# cpu-68008.net
KiCad netlist of a schematic drawn in EAGLE
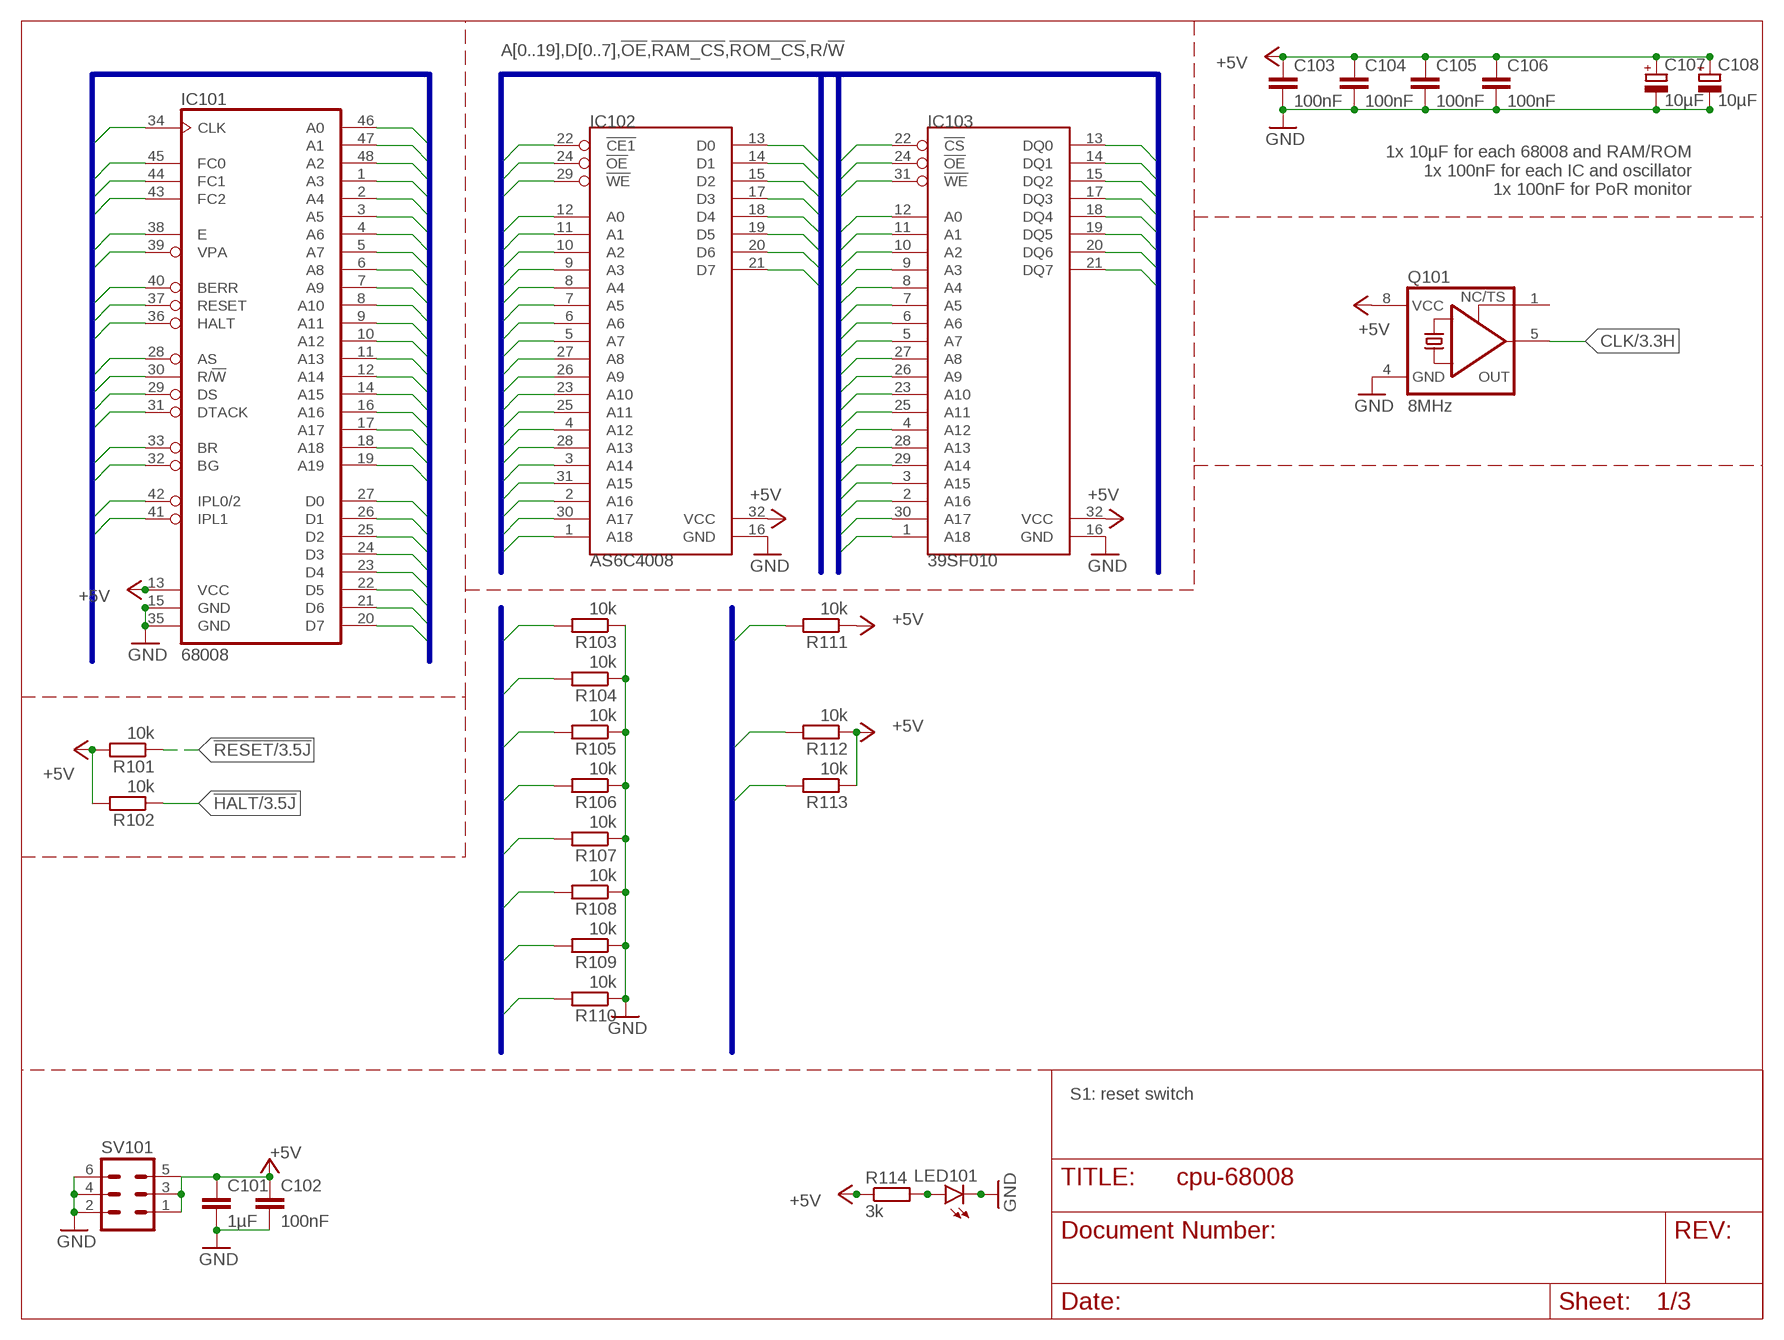
[diagram p0: schematic, sheet 1]
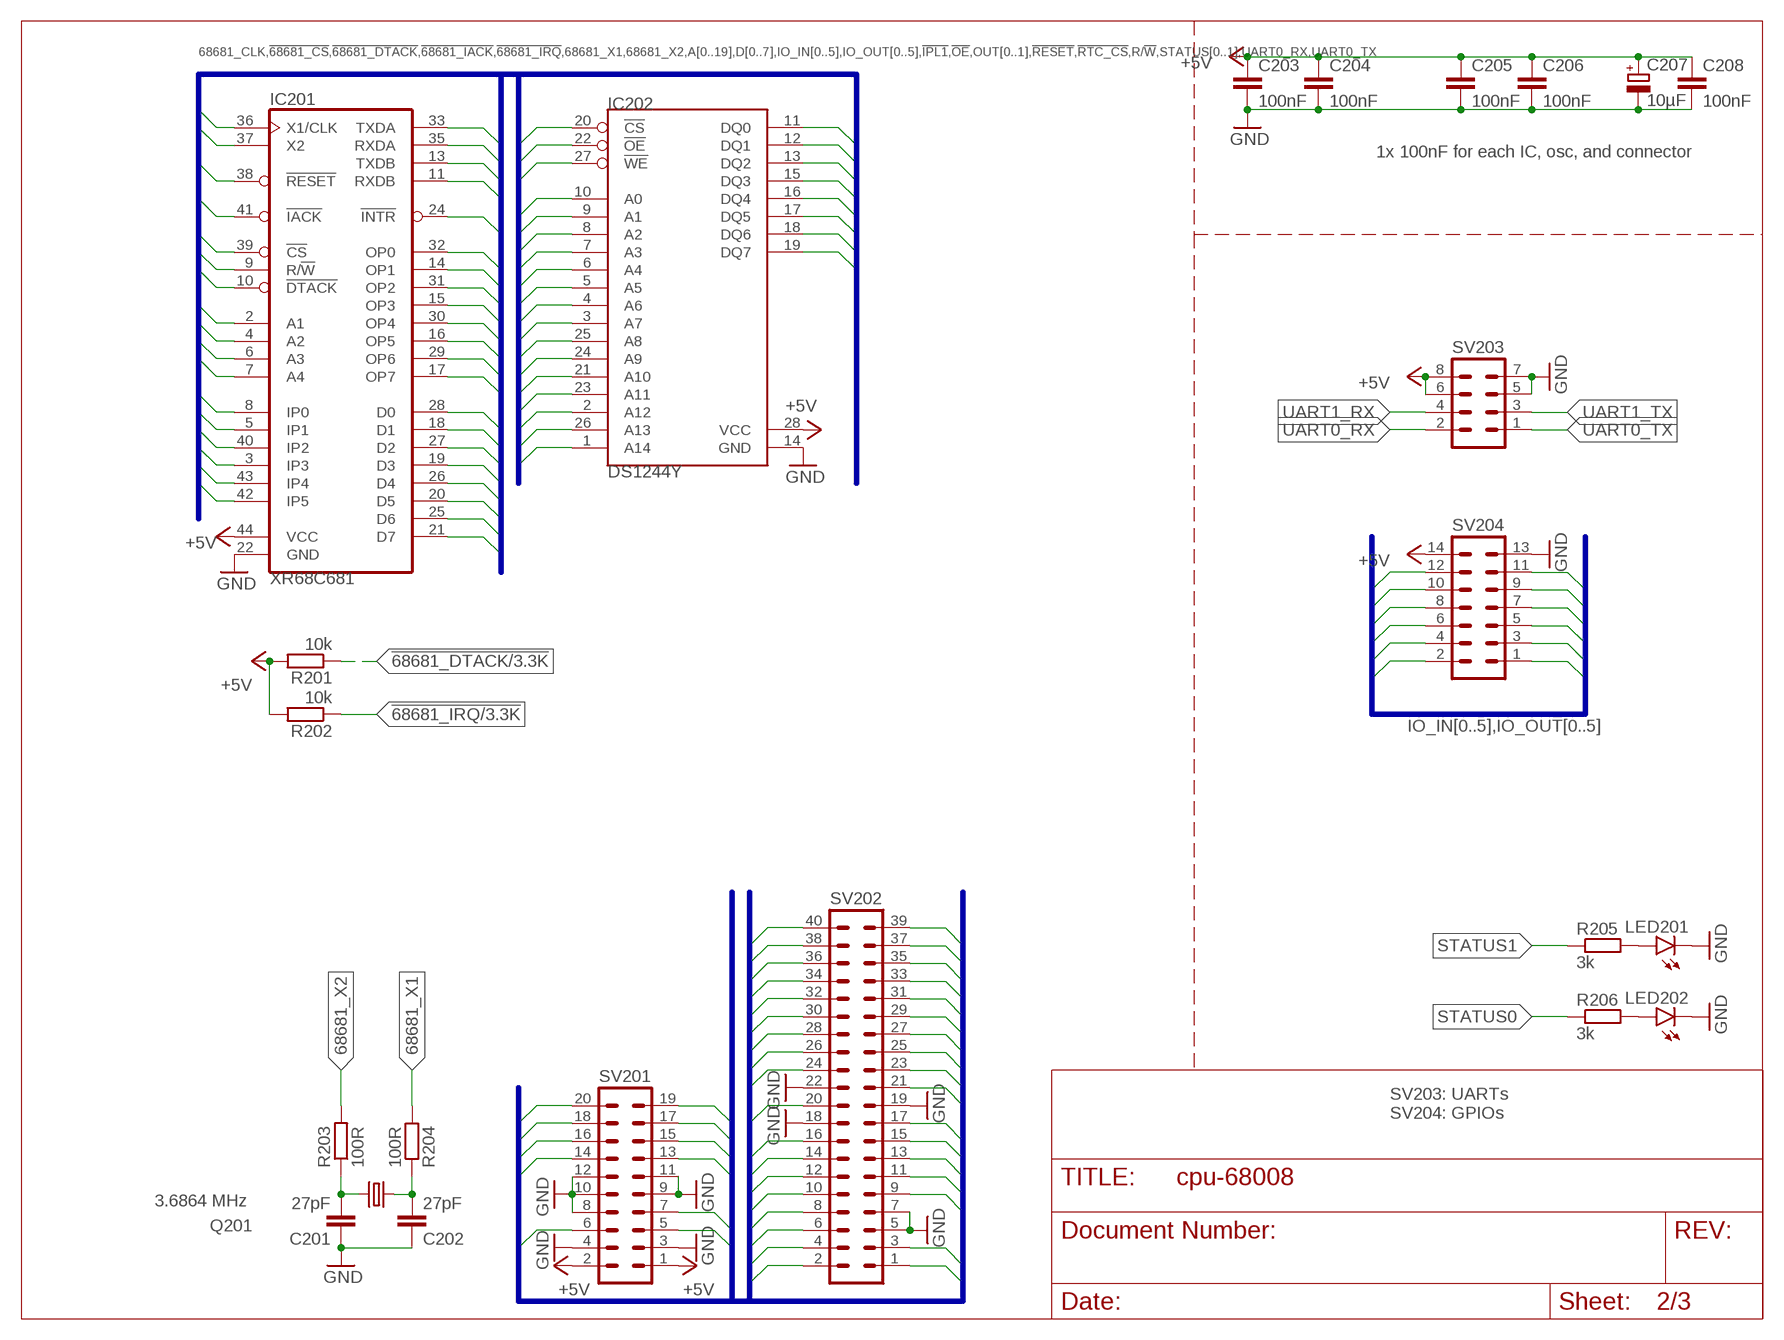
[diagram p1: schematic, sheet 2]
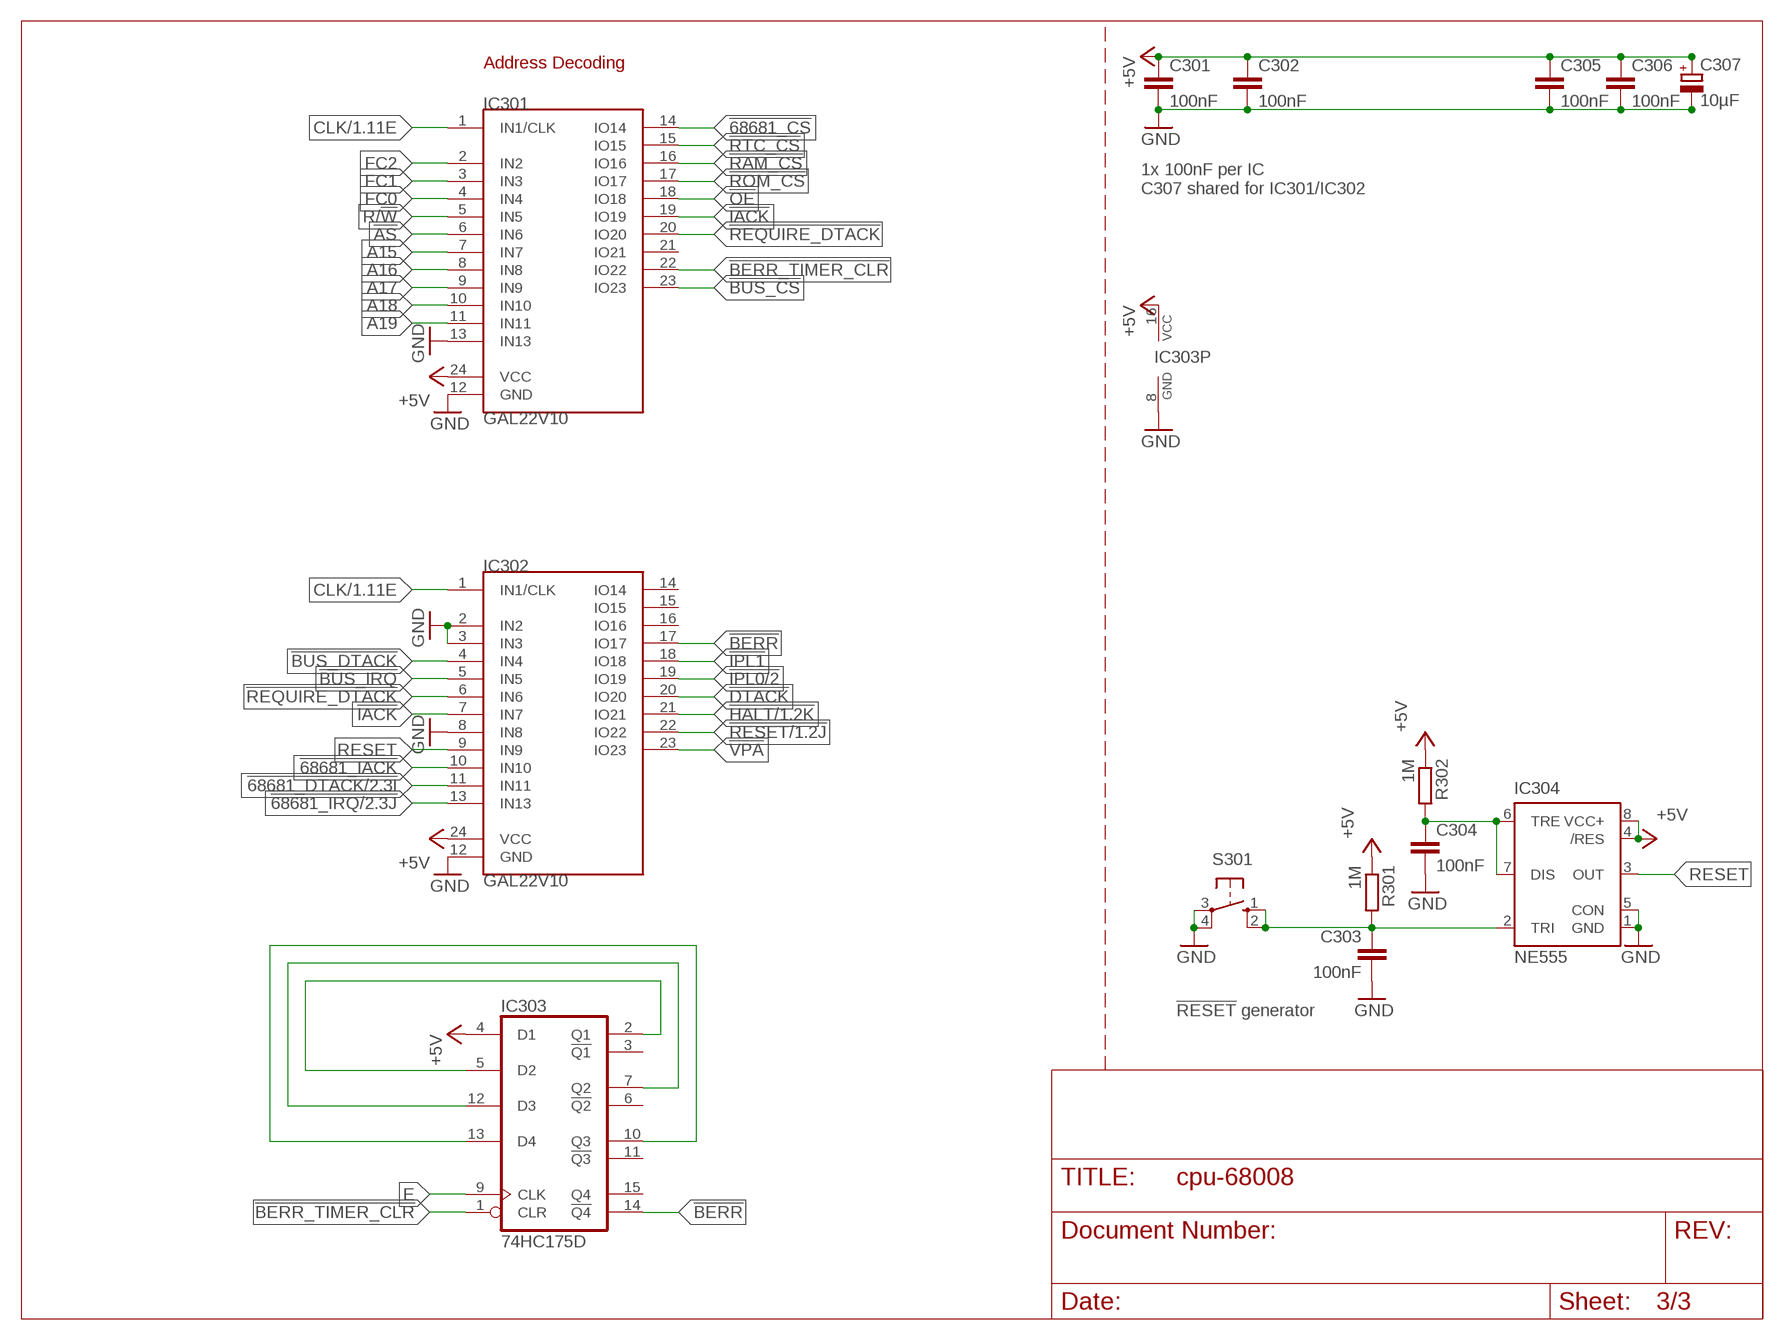
[diagram p2: schematic, sheet 3]

(export (version "E")
  (design (tool "Eeschema 10.0.6"))
  (components
    (comp (ref "C201")
      (value "27pF")
      (footprint "eagle-import:C0805")
      (libsource (lib "eagle-import") (part "C-EUC0805"))
    )
    (comp (ref "C202")
      (value "27pF")
      (footprint "eagle-import:C0805")
      (libsource (lib "eagle-import") (part "C-EUC0805"))
    )
    (comp (ref "C203")
      (value "100nF")
      (footprint "eagle-import:C0805")
      (libsource (lib "eagle-import") (part "C-EUC0805"))
    )
    (comp (ref "C204")
      (value "100nF")
      (footprint "eagle-import:C0805")
      (libsource (lib "eagle-import") (part "C-EUC0805"))
    )
    (comp (ref "C205")
      (value "100nF")
      (footprint "eagle-import:C0805")
      (libsource (lib "eagle-import") (part "C-EUC0805"))
    )
    (comp (ref "C206")
      (value "100nF")
      (footprint "eagle-import:C0805")
      (libsource (lib "eagle-import") (part "C-EUC0805"))
    )
    (comp (ref "C207")
      (value "10µF")
      (footprint "eagle-import:SMC_B")
      (libsource (lib "eagle-import") (part "CPOL-EUSMCB"))
    )
    (comp (ref "C208")
      (value "100nF")
      (footprint "eagle-import:C0805")
      (libsource (lib "eagle-import") (part "C-EUC0805"))
    )
    (comp (ref "IC201")
      (value "XR68C681")
      (footprint "eagle-import:PLCC-S44")
      (libsource (lib "eagle-import") (part "MC68681PLCC44-SOCKET"))
    )
    (comp (ref "IC202")
      (value "DS1244Y")
      (footprint "eagle-import:DIL28-6")
      (libsource (lib "eagle-import") (part "DS1244EDIP-28"))
    )
    (comp (ref "LED201")
      (value "LEDCHIPLED_1206")
      (footprint "eagle-import:CHIPLED_1206")
      (libsource (lib "eagle-import") (part "LEDCHIPLED_1206"))
    )
    (comp (ref "LED202")
      (value "LEDCHIPLED_1206")
      (footprint "eagle-import:CHIPLED_1206")
      (libsource (lib "eagle-import") (part "LEDCHIPLED_1206"))
    )
    (comp (ref "Q201")
      (value "3.6864 MHz")
      (footprint "eagle-import:HC49_S")
      (libsource (lib "eagle-import") (part "CRYSTALHC49S"))
    )
    (comp (ref "R201")
      (value "10k")
      (footprint "eagle-import:R2012")
      (libsource (lib "eagle-import") (part "R-EU_R2012"))
    )
    (comp (ref "R202")
      (value "10k")
      (footprint "eagle-import:R2012")
      (libsource (lib "eagle-import") (part "R-EU_R2012"))
    )
    (comp (ref "R203")
      (value "100R")
      (footprint "eagle-import:R2012")
      (libsource (lib "eagle-import") (part "R-EU_R2012"))
    )
    (comp (ref "R204")
      (value "100R")
      (footprint "eagle-import:R2012")
      (libsource (lib "eagle-import") (part "R-EU_R2012"))
    )
    (comp (ref "R205")
      (value "3k")
      (footprint "eagle-import:R2012")
      (libsource (lib "eagle-import") (part "R-EU_R2012"))
    )
    (comp (ref "R206")
      (value "3k")
      (footprint "eagle-import:R2012")
      (libsource (lib "eagle-import") (part "R-EU_R2012"))
    )
    (comp (ref "SV201")
      (value "MA10-2W")
      (footprint "eagle-import:MA10-2W")
      (libsource (lib "eagle-import") (part "MA10-2W"))
    )
    (comp (ref "SV202")
      (value "MA20-2W")
      (footprint "eagle-import:MA20-2W")
      (libsource (lib "eagle-import") (part "MA20-2W"))
    )
    (comp (ref "SV203")
      (value "MA04-2")
      (footprint "eagle-import:MA04-2")
      (libsource (lib "eagle-import") (part "MA04-2"))
    )
    (comp (ref "SV204")
      (value "MA07-2")
      (footprint "eagle-import:MA07-2")
      (libsource (lib "eagle-import") (part "MA07-2"))
    )
    (comp (ref "C101")
      (value "1µF")
      (footprint "eagle-import:C0805")
      (libsource (lib "eagle-import") (part "C-EUC0805"))
    )
    (comp (ref "C102")
      (value "100nF")
      (footprint "eagle-import:C0805")
      (libsource (lib "eagle-import") (part "C-EUC0805"))
    )
    (comp (ref "C103")
      (value "100nF")
      (footprint "eagle-import:C0805")
      (libsource (lib "eagle-import") (part "C-EUC0805"))
    )
    (comp (ref "C104")
      (value "100nF")
      (footprint "eagle-import:C0805")
      (libsource (lib "eagle-import") (part "C-EUC0805"))
    )
    (comp (ref "C105")
      (value "100nF")
      (footprint "eagle-import:C0805")
      (libsource (lib "eagle-import") (part "C-EUC0805"))
    )
    (comp (ref "C106")
      (value "100nF")
      (footprint "eagle-import:C0805")
      (libsource (lib "eagle-import") (part "C-EUC0805"))
    )
    (comp (ref "C107")
      (value "10µF")
      (footprint "eagle-import:SMC_B")
      (libsource (lib "eagle-import") (part "CPOL-EUSMCB"))
    )
    (comp (ref "C108")
      (value "10µF")
      (footprint "eagle-import:SMC_B")
      (libsource (lib "eagle-import") (part "CPOL-EUSMCB"))
    )
    (comp (ref "IC101")
      (value "68008")
      (footprint "eagle-import:DIL48")
      (libsource (lib "eagle-import") (part "MC68008P"))
    )
    (comp (ref "IC102")
      (value "AS6C4008")
      (footprint "eagle-import:DIL32")
      (libsource (lib "eagle-import") (part "AS6C4008"))
    )
    (comp (ref "IC103")
      (value "39SF010")
      (footprint "eagle-import:DIL32")
      (fields (field (name "MOUSER") "804-39SF010A7CPHE"))
      (libsource (lib "eagle-import") (part "SST39SF0X0PDIP32"))
    )
    (comp (ref "LED101")
      (value "LEDCHIPLED_1206")
      (footprint "eagle-import:CHIPLED_1206")
      (libsource (lib "eagle-import") (part "LEDCHIPLED_1206"))
    )
    (comp (ref "Q101")
      (value "8MHz")
      (footprint "eagle-import:DIL08S")
      (libsource (lib "eagle-import") (part "XO-8"))
    )
    (comp (ref "R101")
      (value "10k")
      (footprint "eagle-import:R2012")
      (libsource (lib "eagle-import") (part "R-EU_R2012"))
    )
    (comp (ref "R102")
      (value "10k")
      (footprint "eagle-import:R2012")
      (libsource (lib "eagle-import") (part "R-EU_R2012"))
    )
    (comp (ref "R103")
      (value "10k")
      (footprint "eagle-import:R2012")
      (libsource (lib "eagle-import") (part "R-EU_R2012"))
    )
    (comp (ref "R104")
      (value "10k")
      (footprint "eagle-import:R2012")
      (libsource (lib "eagle-import") (part "R-EU_R2012"))
    )
    (comp (ref "R105")
      (value "10k")
      (footprint "eagle-import:R2012")
      (libsource (lib "eagle-import") (part "R-EU_R2012"))
    )
    (comp (ref "R106")
      (value "10k")
      (footprint "eagle-import:R2012")
      (libsource (lib "eagle-import") (part "R-EU_R2012"))
    )
    (comp (ref "R107")
      (value "10k")
      (footprint "eagle-import:R2012")
      (libsource (lib "eagle-import") (part "R-EU_R2012"))
    )
    (comp (ref "R108")
      (value "10k")
      (footprint "eagle-import:R2012")
      (libsource (lib "eagle-import") (part "R-EU_R2012"))
    )
    (comp (ref "R109")
      (value "10k")
      (footprint "eagle-import:R2012")
      (libsource (lib "eagle-import") (part "R-EU_R2012"))
    )
    (comp (ref "R110")
      (value "10k")
      (footprint "eagle-import:R2012")
      (libsource (lib "eagle-import") (part "R-EU_R2012"))
    )
    (comp (ref "R111")
      (value "10k")
      (footprint "eagle-import:R2012")
      (libsource (lib "eagle-import") (part "R-EU_R2012"))
    )
    (comp (ref "R112")
      (value "10k")
      (footprint "eagle-import:R2012")
      (libsource (lib "eagle-import") (part "R-EU_R2012"))
    )
    (comp (ref "R113")
      (value "10k")
      (footprint "eagle-import:R2012")
      (libsource (lib "eagle-import") (part "R-EU_R2012"))
    )
    (comp (ref "R114")
      (value "3k")
      (footprint "eagle-import:R2012")
      (libsource (lib "eagle-import") (part "R-EU_R2012"))
    )
    (comp (ref "SV101")
      (value "MA03-2")
      (footprint "eagle-import:MA03-2")
      (libsource (lib "eagle-import") (part "MA03-2"))
    )
    (comp (ref "C301")
      (value "100nF")
      (footprint "eagle-import:C0805")
      (libsource (lib "eagle-import") (part "C-EUC0805"))
    )
    (comp (ref "C302")
      (value "100nF")
      (footprint "eagle-import:C0805")
      (libsource (lib "eagle-import") (part "C-EUC0805"))
    )
    (comp (ref "C303")
      (value "100nF")
      (footprint "eagle-import:C0805")
      (libsource (lib "eagle-import") (part "C-EUC0805"))
    )
    (comp (ref "C304")
      (value "100nF")
      (footprint "eagle-import:C0805")
      (libsource (lib "eagle-import") (part "C-EUC0805"))
    )
    (comp (ref "C305")
      (value "100nF")
      (footprint "eagle-import:C0805")
      (libsource (lib "eagle-import") (part "C-EUC0805"))
    )
    (comp (ref "C306")
      (value "100nF")
      (footprint "eagle-import:C0805")
      (libsource (lib "eagle-import") (part "C-EUC0805"))
    )
    (comp (ref "C307")
      (value "10µF")
      (footprint "eagle-import:SMC_B")
      (libsource (lib "eagle-import") (part "CPOL-EUSMCB"))
    )
    (comp (ref "IC301")
      (value "GAL22V10")
      (footprint "eagle-import:DIL24S")
      (libsource (lib "eagle-import") (part "GAL22V10DIP24"))
    )
    (comp (ref "IC302")
      (value "GAL22V10")
      (footprint "eagle-import:DIL24S")
      (libsource (lib "eagle-import") (part "GAL22V10DIP24"))
    )
    (comp (ref "IC303")
      (value "74HC175D")
      (footprint "eagle-import:SO16")
      (fields (field (name "MOUSER") "595-CD74HCT175M"))
      (libsource (lib "eagle-import") (part "74175DHC"))
    )
    (comp (ref "IC304")
      (value "NE555")
      (footprint "eagle-import:DIL-08")
      (fields (field (name "MF") "Arrow Electronics") (field (name "MPN") "NE555N"))
      (libsource (lib "eagle-import") (part "NE555"))
    )
    (comp (ref "R301")
      (value "1M")
      (footprint "eagle-import:R2012")
      (libsource (lib "eagle-import") (part "R-EU_R2012"))
    )
    (comp (ref "R302")
      (value "1M")
      (footprint "eagle-import:R2012")
      (libsource (lib "eagle-import") (part "R-EU_R2012"))
    )
    (comp (ref "S301")
      (value "10-XX")
      (footprint "eagle-import:B3F-10XX")
      (fields (field (name "MPN") "B3F-1000"))
      (libsource (lib "eagle-import") (part "10-XX"))
    )
  )
  (nets
    (net (code "3") (name "+5V") (class "Default")
      (node (ref "C101") (pin "1") (pinfunction "1_1") (pintype "passive"))
      (node (ref "C102") (pin "1") (pinfunction "1_1") (pintype "passive"))
      (node (ref "C103") (pin "1") (pinfunction "1_1") (pintype "passive"))
      (node (ref "C104") (pin "1") (pinfunction "1_1") (pintype "passive"))
      (node (ref "C105") (pin "1") (pinfunction "1_1") (pintype "passive"))
      (node (ref "C106") (pin "1") (pinfunction "1_1") (pintype "passive"))
      (node (ref "C107") (pin "+") (pinfunction "+_+") (pintype "passive"))
      (node (ref "C108") (pin "+") (pinfunction "+_+") (pintype "passive"))
      (node (ref "C203") (pin "1") (pinfunction "1_1") (pintype "passive"))
      (node (ref "C204") (pin "1") (pinfunction "1_1") (pintype "passive"))
      (node (ref "C205") (pin "1") (pinfunction "1_1") (pintype "passive"))
      (node (ref "C206") (pin "1") (pinfunction "1_1") (pintype "passive"))
      (node (ref "C207") (pin "+") (pinfunction "+_+") (pintype "passive"))
      (node (ref "C208") (pin "1") (pinfunction "1_1") (pintype "passive"))
      (node (ref "C301") (pin "1") (pinfunction "1_1") (pintype "passive"))
      (node (ref "C302") (pin "1") (pinfunction "1_1") (pintype "passive"))
      (node (ref "C305") (pin "1") (pinfunction "1_1") (pintype "passive"))
      (node (ref "C306") (pin "1") (pinfunction "1_1") (pintype "passive"))
      (node (ref "C307") (pin "+") (pinfunction "+_+") (pintype "passive"))
      (node (ref "IC101") (pin "13") (pinfunction "VCC_13") (pintype "power_in"))
      (node (ref "IC102") (pin "32") (pinfunction "VCC_32") (pintype "power_in"))
      (node (ref "IC103") (pin "32") (pinfunction "VCC_32") (pintype "power_in"))
      (node (ref "IC201") (pin "44") (pinfunction "VCC_44") (pintype "power_in"))
      (node (ref "IC202") (pin "28") (pinfunction "VCC_28") (pintype "power_in"))
      (node (ref "IC301") (pin "24") (pinfunction "VCC_24") (pintype "power_in"))
      (node (ref "IC302") (pin "24") (pinfunction "VCC_24") (pintype "power_in"))
      (node (ref "IC303") (pin "16") (pinfunction "VCC_16") (pintype "power_in"))
      (node (ref "IC303") (pin "4") (pinfunction "D1_4") (pintype "input"))
      (node (ref "IC304") (pin "4") (pinfunction "/RES_4") (pintype "input"))
      (node (ref "IC304") (pin "8") (pinfunction "VCC+_8") (pintype "power_in"))
      (node (ref "Q101") (pin "8") (pinfunction "VCC_8") (pintype "power_in"))
      (node (ref "R101") (pin "2") (pinfunction "2_2") (pintype "passive"))
      (node (ref "R102") (pin "2") (pinfunction "2_2") (pintype "passive"))
      (node (ref "R111") (pin "1") (pinfunction "1_1") (pintype "passive"))
      (node (ref "R112") (pin "1") (pinfunction "1_1") (pintype "passive"))
      (node (ref "R113") (pin "1") (pinfunction "1_1") (pintype "passive"))
      (node (ref "R114") (pin "1") (pinfunction "1_1") (pintype "passive"))
      (node (ref "R201") (pin "2") (pinfunction "2_2") (pintype "passive"))
      (node (ref "R202") (pin "2") (pinfunction "2_2") (pintype "passive"))
      (node (ref "R301") (pin "1") (pinfunction "1_1") (pintype "passive"))
      (node (ref "R302") (pin "1") (pinfunction "1_1") (pintype "passive"))
      (node (ref "SV101") (pin "1") (pinfunction "1_1") (pintype "passive"))
      (node (ref "SV101") (pin "3") (pinfunction "3_3") (pintype "passive"))
      (node (ref "SV101") (pin "5") (pinfunction "5_5") (pintype "passive"))
      (node (ref "SV201") (pin "1") (pinfunction "1_1") (pintype "passive"))
      (node (ref "SV201") (pin "2") (pinfunction "2_2") (pintype "passive"))
      (node (ref "SV203") (pin "6") (pinfunction "6_6") (pintype "passive"))
      (node (ref "SV203") (pin "8") (pinfunction "8_8") (pintype "passive"))
      (node (ref "SV204") (pin "14") (pinfunction "14_14") (pintype "passive"))
    )
    (net (code "7") (name "68681_X1") (class "Default")
      (node (ref "IC201") (pin "36") (pinfunction "X1/CLK_36") (pintype "input"))
      (node (ref "R204") (pin "2") (pinfunction "2_2") (pintype "passive"))
    )
    (net (code "8") (name "68681_X2") (class "Default")
      (node (ref "IC201") (pin "37") (pinfunction "X2_37") (pintype "output"))
      (node (ref "R203") (pin "2") (pinfunction "2_2") (pintype "passive"))
    )
    (net (code "9") (name "A0") (class "Default")
      (node (ref "IC101") (pin "46") (pinfunction "A0_46") (pintype "output"))
      (node (ref "IC102") (pin "12") (pinfunction "A0_12") (pintype "input"))
      (node (ref "IC103") (pin "12") (pinfunction "A0_12") (pintype "input"))
      (node (ref "IC201") (pin "2") (pinfunction "A1_2") (pintype "input"))
      (node (ref "IC202") (pin "10") (pinfunction "A0_10") (pintype "input"))
      (node (ref "SV201") (pin "17") (pinfunction "17_17") (pintype "passive"))
    )
    (net (code "10") (name "A1") (class "Default")
      (node (ref "IC101") (pin "47") (pinfunction "A1_47") (pintype "output"))
      (node (ref "IC102") (pin "11") (pinfunction "A1_11") (pintype "input"))
      (node (ref "IC103") (pin "11") (pinfunction "A1_11") (pintype "input"))
      (node (ref "IC201") (pin "4") (pinfunction "A2_4") (pintype "input"))
      (node (ref "IC202") (pin "9") (pinfunction "A1_9") (pintype "input"))
      (node (ref "SV201") (pin "15") (pinfunction "15_15") (pintype "passive"))
    )
    (net (code "11") (name "A2") (class "Default")
      (node (ref "IC101") (pin "48") (pinfunction "A2_48") (pintype "output"))
      (node (ref "IC102") (pin "10") (pinfunction "A2_10") (pintype "input"))
      (node (ref "IC103") (pin "10") (pinfunction "A2_10") (pintype "input"))
      (node (ref "IC201") (pin "6") (pinfunction "A3_6") (pintype "input"))
      (node (ref "IC202") (pin "8") (pinfunction "A2_8") (pintype "input"))
      (node (ref "SV201") (pin "13") (pinfunction "13_13") (pintype "passive"))
    )
    (net (code "12") (name "A3") (class "Default")
      (node (ref "IC101") (pin "1") (pinfunction "A3_1") (pintype "output"))
      (node (ref "IC102") (pin "9") (pinfunction "A3_9") (pintype "input"))
      (node (ref "IC103") (pin "9") (pinfunction "A3_9") (pintype "input"))
      (node (ref "IC201") (pin "7") (pinfunction "A4_7") (pintype "input"))
      (node (ref "IC202") (pin "7") (pinfunction "A3_7") (pintype "input"))
      (node (ref "SV201") (pin "14") (pinfunction "14_14") (pintype "passive"))
    )
    (net (code "13") (name "A4") (class "Default")
      (node (ref "IC101") (pin "2") (pinfunction "A4_2") (pintype "output"))
      (node (ref "IC102") (pin "8") (pinfunction "A4_8") (pintype "input"))
      (node (ref "IC103") (pin "8") (pinfunction "A4_8") (pintype "input"))
      (node (ref "IC202") (pin "6") (pinfunction "A4_6") (pintype "input"))
      (node (ref "SV201") (pin "16") (pinfunction "16_16") (pintype "passive"))
    )
    (net (code "14") (name "A5") (class "Default")
      (node (ref "IC101") (pin "3") (pinfunction "A5_3") (pintype "output"))
      (node (ref "IC102") (pin "7") (pinfunction "A5_7") (pintype "input"))
      (node (ref "IC103") (pin "7") (pinfunction "A5_7") (pintype "input"))
      (node (ref "IC202") (pin "5") (pinfunction "A5_5") (pintype "input"))
      (node (ref "SV201") (pin "18") (pinfunction "18_18") (pintype "passive"))
    )
    (net (code "15") (name "A6") (class "Default")
      (node (ref "IC101") (pin "4") (pinfunction "A6_4") (pintype "output"))
      (node (ref "IC102") (pin "6") (pinfunction "A6_6") (pintype "input"))
      (node (ref "IC103") (pin "6") (pinfunction "A6_6") (pintype "input"))
      (node (ref "IC202") (pin "4") (pinfunction "A6_4") (pintype "input"))
      (node (ref "SV201") (pin "20") (pinfunction "20_20") (pintype "passive"))
    )
    (net (code "16") (name "A7") (class "Default")
      (node (ref "IC101") (pin "5") (pinfunction "A7_5") (pintype "output"))
      (node (ref "IC102") (pin "5") (pinfunction "A7_5") (pintype "input"))
      (node (ref "IC103") (pin "5") (pinfunction "A7_5") (pintype "input"))
      (node (ref "IC202") (pin "3") (pinfunction "A7_3") (pintype "input"))
      (node (ref "SV202") (pin "2") (pinfunction "2_2") (pintype "passive"))
    )
    (net (code "17") (name "A8") (class "Default")
      (node (ref "IC101") (pin "6") (pinfunction "A8_6") (pintype "output"))
      (node (ref "IC102") (pin "27") (pinfunction "A8_27") (pintype "input"))
      (node (ref "IC103") (pin "27") (pinfunction "A8_27") (pintype "input"))
      (node (ref "IC202") (pin "25") (pinfunction "A8_25") (pintype "input"))
      (node (ref "SV202") (pin "4") (pinfunction "4_4") (pintype "passive"))
    )
    (net (code "18") (name "A9") (class "Default")
      (node (ref "IC101") (pin "7") (pinfunction "A9_7") (pintype "output"))
      (node (ref "IC102") (pin "26") (pinfunction "A9_26") (pintype "input"))
      (node (ref "IC103") (pin "26") (pinfunction "A9_26") (pintype "input"))
      (node (ref "IC202") (pin "24") (pinfunction "A9_24") (pintype "input"))
      (node (ref "SV202") (pin "6") (pinfunction "6_6") (pintype "passive"))
    )
    (net (code "19") (name "A10") (class "Default")
      (node (ref "IC101") (pin "8") (pinfunction "A10_8") (pintype "output"))
      (node (ref "IC102") (pin "23") (pinfunction "A10_23") (pintype "input"))
      (node (ref "IC103") (pin "23") (pinfunction "A10_23") (pintype "input"))
      (node (ref "IC202") (pin "21") (pinfunction "A10_21") (pintype "input"))
      (node (ref "SV202") (pin "8") (pinfunction "8_8") (pintype "passive"))
    )
    (net (code "20") (name "A11") (class "Default")
      (node (ref "IC101") (pin "9") (pinfunction "A11_9") (pintype "output"))
      (node (ref "IC102") (pin "25") (pinfunction "A11_25") (pintype "input"))
      (node (ref "IC103") (pin "25") (pinfunction "A11_25") (pintype "input"))
      (node (ref "IC202") (pin "23") (pinfunction "A11_23") (pintype "input"))
      (node (ref "SV202") (pin "10") (pinfunction "10_10") (pintype "passive"))
    )
    (net (code "21") (name "A12") (class "Default")
      (node (ref "IC101") (pin "10") (pinfunction "A12_10") (pintype "output"))
      (node (ref "IC102") (pin "4") (pinfunction "A12_4") (pintype "input"))
      (node (ref "IC103") (pin "4") (pinfunction "A12_4") (pintype "input"))
      (node (ref "IC202") (pin "2") (pinfunction "A12_2") (pintype "input"))
      (node (ref "SV202") (pin "12") (pinfunction "12_12") (pintype "passive"))
    )
    (net (code "22") (name "A13") (class "Default")
      (node (ref "IC101") (pin "11") (pinfunction "A13_11") (pintype "output"))
      (node (ref "IC102") (pin "28") (pinfunction "A13_28") (pintype "input"))
      (node (ref "IC103") (pin "28") (pinfunction "A13_28") (pintype "input"))
      (node (ref "IC202") (pin "26") (pinfunction "A13_26") (pintype "input"))
      (node (ref "SV202") (pin "14") (pinfunction "14_14") (pintype "passive"))
    )
    (net (code "23") (name "A14") (class "Default")
      (node (ref "IC101") (pin "12") (pinfunction "A14_12") (pintype "output"))
      (node (ref "IC102") (pin "3") (pinfunction "A14_3") (pintype "input"))
      (node (ref "IC103") (pin "29") (pinfunction "A14_29") (pintype "input"))
      (node (ref "IC202") (pin "1") (pinfunction "A14_1") (pintype "input"))
      (node (ref "SV202") (pin "16") (pinfunction "16_16") (pintype "passive"))
    )
    (net (code "24") (name "A15") (class "Default")
      (node (ref "IC101") (pin "14") (pinfunction "A15_14") (pintype "output"))
      (node (ref "IC102") (pin "31") (pinfunction "A15_31") (pintype "input"))
      (node (ref "IC103") (pin "3") (pinfunction "A15_3") (pintype "input"))
      (node (ref "IC301") (pin "7") (pinfunction "IN7_7") (pintype "input"))
      (node (ref "SV202") (pin "20") (pinfunction "20_20") (pintype "passive"))
    )
    (net (code "25") (name "A16") (class "Default")
      (node (ref "IC101") (pin "16") (pinfunction "A16_16") (pintype "output"))
      (node (ref "IC102") (pin "2") (pinfunction "A16_2") (pintype "input"))
      (node (ref "IC103") (pin "2") (pinfunction "A16_2") (pintype "input"))
      (node (ref "IC301") (pin "8") (pinfunction "IN8_8") (pintype "input"))
      (node (ref "SV202") (pin "24") (pinfunction "24_24") (pintype "passive"))
    )
    (net (code "26") (name "A17") (class "Default")
      (node (ref "IC101") (pin "17") (pinfunction "A17_17") (pintype "output"))
      (node (ref "IC102") (pin "30") (pinfunction "A17_30") (pintype "input"))
      (node (ref "IC103") (pin "30") (pinfunction "A17_30") (pintype "input"))
      (node (ref "IC301") (pin "9") (pinfunction "IN9_9") (pintype "input"))
      (node (ref "SV202") (pin "26") (pinfunction "26_26") (pintype "passive"))
    )
    (net (code "27") (name "A18") (class "Default")
      (node (ref "IC101") (pin "18") (pinfunction "A18_18") (pintype "output"))
      (node (ref "IC102") (pin "1") (pinfunction "A18_1") (pintype "input"))
      (node (ref "IC103") (pin "1") (pinfunction "A18_1") (pintype "input"))
      (node (ref "IC301") (pin "10") (pinfunction "IN10_10") (pintype "input"))
      (node (ref "SV202") (pin "28") (pinfunction "28_28") (pintype "passive"))
    )
    (net (code "28") (name "A19") (class "Default")
      (node (ref "IC101") (pin "19") (pinfunction "A19_19") (pintype "output"))
      (node (ref "IC301") (pin "11") (pinfunction "IN11_11") (pintype "input"))
      (node (ref "SV202") (pin "30") (pinfunction "30_30") (pintype "passive"))
    )
    (net (code "29") (name "CLK") (class "Default")
      (node (ref "IC101") (pin "34") (pinfunction "CLK_34") (pintype "input"))
      (node (ref "IC301") (pin "1") (pinfunction "IN1/CLK_1") (pintype "input"))
      (node (ref "IC302") (pin "1") (pinfunction "IN1/CLK_1") (pintype "input"))
      (node (ref "Q101") (pin "5") (pinfunction "OUT_5") (pintype "output"))
      (node (ref "SV202") (pin "21") (pinfunction "21_21") (pintype "passive"))
    )
    (net (code "30") (name "D0") (class "Default")
      (node (ref "IC101") (pin "27") (pinfunction "D0_27") (pintype "bidirectional"))
      (node (ref "IC102") (pin "13") (pinfunction "D0_13") (pintype "bidirectional"))
      (node (ref "IC103") (pin "13") (pinfunction "DQ0_13") (pintype "bidirectional"))
      (node (ref "IC201") (pin "28") (pinfunction "D0_28") (pintype "bidirectional"))
      (node (ref "IC202") (pin "11") (pinfunction "DQ0_11") (pintype "bidirectional"))
      (node (ref "R103") (pin "2") (pinfunction "2_2") (pintype "passive"))
      (node (ref "SV202") (pin "35") (pinfunction "35_35") (pintype "passive"))
    )
    (net (code "31") (name "D1") (class "Default")
      (node (ref "IC101") (pin "26") (pinfunction "D1_26") (pintype "bidirectional"))
      (node (ref "IC102") (pin "14") (pinfunction "D1_14") (pintype "bidirectional"))
      (node (ref "IC103") (pin "14") (pinfunction "DQ1_14") (pintype "bidirectional"))
      (node (ref "IC201") (pin "18") (pinfunction "D1_18") (pintype "bidirectional"))
      (node (ref "IC202") (pin "12") (pinfunction "DQ1_12") (pintype "bidirectional"))
      (node (ref "R104") (pin "2") (pinfunction "2_2") (pintype "passive"))
      (node (ref "SV202") (pin "37") (pinfunction "37_37") (pintype "passive"))
    )
    (net (code "32") (name "D2") (class "Default")
      (node (ref "IC101") (pin "25") (pinfunction "D2_25") (pintype "bidirectional"))
      (node (ref "IC102") (pin "15") (pinfunction "D2_15") (pintype "bidirectional"))
      (node (ref "IC103") (pin "15") (pinfunction "DQ2_15") (pintype "bidirectional"))
      (node (ref "IC201") (pin "27") (pinfunction "D2_27") (pintype "bidirectional"))
      (node (ref "IC202") (pin "13") (pinfunction "DQ2_13") (pintype "bidirectional"))
      (node (ref "R105") (pin "2") (pinfunction "2_2") (pintype "passive"))
      (node (ref "SV202") (pin "39") (pinfunction "39_39") (pintype "passive"))
    )
    (net (code "33") (name "D3") (class "Default")
      (node (ref "IC101") (pin "24") (pinfunction "D3_24") (pintype "bidirectional"))
      (node (ref "IC102") (pin "17") (pinfunction "D3_17") (pintype "bidirectional"))
      (node (ref "IC103") (pin "17") (pinfunction "DQ3_17") (pintype "bidirectional"))
      (node (ref "IC201") (pin "19") (pinfunction "D3_19") (pintype "bidirectional"))
      (node (ref "IC202") (pin "15") (pinfunction "DQ3_15") (pintype "bidirectional"))
      (node (ref "R106") (pin "2") (pinfunction "2_2") (pintype "passive"))
      (node (ref "SV202") (pin "40") (pinfunction "40_40") (pintype "passive"))
    )
    (net (code "34") (name "D4") (class "Default")
      (node (ref "IC101") (pin "23") (pinfunction "D4_23") (pintype "bidirectional"))
      (node (ref "IC102") (pin "18") (pinfunction "D4_18") (pintype "bidirectional"))
      (node (ref "IC103") (pin "18") (pinfunction "DQ4_18") (pintype "bidirectional"))
      (node (ref "IC201") (pin "26") (pinfunction "D4_26") (pintype "bidirectional"))
      (node (ref "IC202") (pin "16") (pinfunction "DQ4_16") (pintype "bidirectional"))
      (node (ref "R107") (pin "2") (pinfunction "2_2") (pintype "passive"))
      (node (ref "SV202") (pin "38") (pinfunction "38_38") (pintype "passive"))
    )
    (net (code "35") (name "D5") (class "Default")
      (node (ref "IC101") (pin "22") (pinfunction "D5_22") (pintype "bidirectional"))
      (node (ref "IC102") (pin "19") (pinfunction "D5_19") (pintype "bidirectional"))
      (node (ref "IC103") (pin "19") (pinfunction "DQ5_19") (pintype "bidirectional"))
      (node (ref "IC201") (pin "20") (pinfunction "D5_20") (pintype "bidirectional"))
      (node (ref "IC202") (pin "17") (pinfunction "DQ5_17") (pintype "bidirectional"))
      (node (ref "R108") (pin "2") (pinfunction "2_2") (pintype "passive"))
      (node (ref "SV202") (pin "36") (pinfunction "36_36") (pintype "passive"))
    )
    (net (code "36") (name "D6") (class "Default")
      (node (ref "IC101") (pin "21") (pinfunction "D6_21") (pintype "bidirectional"))
      (node (ref "IC102") (pin "20") (pinfunction "D6_20") (pintype "bidirectional"))
      (node (ref "IC103") (pin "20") (pinfunction "DQ6_20") (pintype "bidirectional"))
      (node (ref "IC201") (pin "25") (pinfunction "D6_25") (pintype "bidirectional"))
      (node (ref "IC202") (pin "18") (pinfunction "DQ6_18") (pintype "bidirectional"))
      (node (ref "R109") (pin "2") (pinfunction "2_2") (pintype "passive"))
      (node (ref "SV202") (pin "34") (pinfunction "34_34") (pintype "passive"))
    )
    (net (code "37") (name "D7") (class "Default")
      (node (ref "IC101") (pin "20") (pinfunction "D7_20") (pintype "bidirectional"))
      (node (ref "IC102") (pin "21") (pinfunction "D7_21") (pintype "bidirectional"))
      (node (ref "IC103") (pin "21") (pinfunction "DQ7_21") (pintype "bidirectional"))
      (node (ref "IC201") (pin "21") (pinfunction "D7_21") (pintype "bidirectional"))
      (node (ref "IC202") (pin "19") (pinfunction "DQ7_19") (pintype "bidirectional"))
      (node (ref "R110") (pin "2") (pinfunction "2_2") (pintype "passive"))
      (node (ref "SV202") (pin "32") (pinfunction "32_32") (pintype "passive"))
    )
    (net (code "38") (name "E") (class "Default")
      (node (ref "IC101") (pin "38") (pinfunction "E_38") (pintype "output"))
      (node (ref "IC303") (pin "9") (pinfunction "CLK_9") (pintype "input"))
      (node (ref "SV202") (pin "13") (pinfunction "13_13") (pintype "passive"))
    )
    (net (code "39") (name "FC0") (class "Default")
      (node (ref "IC101") (pin "45") (pinfunction "FC0_45") (pintype "output"))
      (node (ref "IC301") (pin "4") (pinfunction "IN4_4") (pintype "input"))
      (node (ref "SV201") (pin "19") (pinfunction "19_19") (pintype "passive"))
    )
    (net (code "40") (name "FC1") (class "Default")
      (node (ref "IC101") (pin "44") (pinfunction "FC1_44") (pintype "output"))
      (node (ref "IC301") (pin "3") (pinfunction "IN3_3") (pintype "input"))
      (node (ref "SV202") (pin "1") (pinfunction "1_1") (pintype "passive"))
    )
    (net (code "41") (name "FC2") (class "Default")
      (node (ref "IC101") (pin "43") (pinfunction "FC2_43") (pintype "output"))
      (node (ref "IC301") (pin "2") (pinfunction "IN2_2") (pintype "input"))
      (node (ref "SV202") (pin "3") (pinfunction "3_3") (pintype "passive"))
    )
    (net (code "42") (name "GND") (class "Default")
      (node (ref "C101") (pin "2") (pinfunction "2_2") (pintype "passive"))
      (node (ref "C102") (pin "2") (pinfunction "2_2") (pintype "passive"))
      (node (ref "C103") (pin "2") (pinfunction "2_2") (pintype "passive"))
      (node (ref "C104") (pin "2") (pinfunction "2_2") (pintype "passive"))
      (node (ref "C105") (pin "2") (pinfunction "2_2") (pintype "passive"))
      (node (ref "C106") (pin "2") (pinfunction "2_2") (pintype "passive"))
      (node (ref "C107") (pin "-") (pinfunction "-_-") (pintype "passive"))
      (node (ref "C108") (pin "-") (pinfunction "-_-") (pintype "passive"))
      (node (ref "C201") (pin "1") (pinfunction "1_1") (pintype "passive"))
      (node (ref "C202") (pin "1") (pinfunction "1_1") (pintype "passive"))
      (node (ref "C203") (pin "2") (pinfunction "2_2") (pintype "passive"))
      (node (ref "C204") (pin "2") (pinfunction "2_2") (pintype "passive"))
      (node (ref "C205") (pin "2") (pinfunction "2_2") (pintype "passive"))
      (node (ref "C206") (pin "2") (pinfunction "2_2") (pintype "passive"))
      (node (ref "C207") (pin "-") (pinfunction "-_-") (pintype "passive"))
      (node (ref "C208") (pin "2") (pinfunction "2_2") (pintype "passive"))
      (node (ref "C301") (pin "2") (pinfunction "2_2") (pintype "passive"))
      (node (ref "C302") (pin "2") (pinfunction "2_2") (pintype "passive"))
      (node (ref "C303") (pin "2") (pinfunction "2_2") (pintype "passive"))
      (node (ref "C304") (pin "2") (pinfunction "2_2") (pintype "passive"))
      (node (ref "C305") (pin "2") (pinfunction "2_2") (pintype "passive"))
      (node (ref "C306") (pin "2") (pinfunction "2_2") (pintype "passive"))
      (node (ref "C307") (pin "-") (pinfunction "-_-") (pintype "passive"))
      (node (ref "IC101") (pin "15") (pinfunction "GND_15") (pintype "power_in"))
      (node (ref "IC101") (pin "35") (pinfunction "GND_35") (pintype "power_in"))
      (node (ref "IC102") (pin "16") (pinfunction "GND_16") (pintype "power_in"))
      (node (ref "IC103") (pin "16") (pinfunction "GND_16") (pintype "power_in"))
      (node (ref "IC201") (pin "22") (pinfunction "GND_22") (pintype "power_in"))
      (node (ref "IC202") (pin "14") (pinfunction "GND_14") (pintype "power_in"))
      (node (ref "IC301") (pin "12") (pinfunction "GND_12") (pintype "power_in"))
      (node (ref "IC301") (pin "13") (pinfunction "IN13_13") (pintype "input"))
      (node (ref "IC302") (pin "12") (pinfunction "GND_12") (pintype "power_in"))
      (node (ref "IC302") (pin "2") (pinfunction "IN2_2") (pintype "input"))
      (node (ref "IC302") (pin "3") (pinfunction "IN3_3") (pintype "input"))
      (node (ref "IC302") (pin "8") (pinfunction "IN8_8") (pintype "input"))
      (node (ref "IC303") (pin "8") (pinfunction "GND_8") (pintype "power_in"))
      (node (ref "IC304") (pin "1") (pinfunction "GND_1") (pintype "power_in"))
      (node (ref "IC304") (pin "5") (pinfunction "CON_5") (pintype "input"))
      (node (ref "LED101") (pin "C") (pinfunction "C_C") (pintype "passive"))
      (node (ref "LED201") (pin "C") (pinfunction "C_C") (pintype "passive"))
      (node (ref "LED202") (pin "C") (pinfunction "C_C") (pintype "passive"))
      (node (ref "Q101") (pin "4") (pinfunction "GND_4") (pintype "power_in"))
      (node (ref "R103") (pin "1") (pinfunction "1_1") (pintype "passive"))
      (node (ref "R104") (pin "1") (pinfunction "1_1") (pintype "passive"))
      (node (ref "R105") (pin "1") (pinfunction "1_1") (pintype "passive"))
      (node (ref "R106") (pin "1") (pinfunction "1_1") (pintype "passive"))
      (node (ref "R107") (pin "1") (pinfunction "1_1") (pintype "passive"))
      (node (ref "R108") (pin "1") (pinfunction "1_1") (pintype "passive"))
      (node (ref "R109") (pin "1") (pinfunction "1_1") (pintype "passive"))
      (node (ref "R110") (pin "1") (pinfunction "1_1") (pintype "passive"))
      (node (ref "S301") (pin "3") (pinfunction "P_3") (pintype "passive"))
      (node (ref "S301") (pin "4") (pinfunction "P1_4") (pintype "passive"))
      (node (ref "SV101") (pin "2") (pinfunction "2_2") (pintype "passive"))
      (node (ref "SV101") (pin "4") (pinfunction "4_4") (pintype "passive"))
      (node (ref "SV101") (pin "6") (pinfunction "6_6") (pintype "passive"))
      (node (ref "SV201") (pin "10") (pinfunction "10_10") (pintype "passive"))
      (node (ref "SV201") (pin "11") (pinfunction "11_11") (pintype "passive"))
      (node (ref "SV201") (pin "12") (pinfunction "12_12") (pintype "passive"))
      (node (ref "SV201") (pin "3") (pinfunction "3_3") (pintype "passive"))
      (node (ref "SV201") (pin "4") (pinfunction "4_4") (pintype "passive"))
      (node (ref "SV201") (pin "8") (pinfunction "8_8") (pintype "passive"))
      (node (ref "SV201") (pin "9") (pinfunction "9_9") (pintype "passive"))
      (node (ref "SV202") (pin "18") (pinfunction "18_18") (pintype "passive"))
      (node (ref "SV202") (pin "19") (pinfunction "19_19") (pintype "passive"))
      (node (ref "SV202") (pin "22") (pinfunction "22_22") (pintype "passive"))
      (node (ref "SV202") (pin "5") (pinfunction "5_5") (pintype "passive"))
      (node (ref "SV202") (pin "7") (pinfunction "7_7") (pintype "passive"))
      (node (ref "SV203") (pin "5") (pinfunction "5_5") (pintype "passive"))
      (node (ref "SV203") (pin "7") (pinfunction "7_7") (pintype "passive"))
      (node (ref "SV204") (pin "13") (pinfunction "13_13") (pintype "passive"))
    )
    (net (code "43") (name "IO_IN0") (class "Default")
      (node (ref "IC201") (pin "40") (pinfunction "IP2_40") (pintype "input"))
      (node (ref "SV204") (pin "12") (pinfunction "12_12") (pintype "passive"))
    )
    (net (code "44") (name "IO_IN1") (class "Default")
      (node (ref "IC201") (pin "42") (pinfunction "IP5_42") (pintype "input"))
      (node (ref "SV204") (pin "10") (pinfunction "10_10") (pintype "passive"))
    )
    (net (code "45") (name "IO_IN2") (class "Default")
      (node (ref "IC201") (pin "43") (pinfunction "IP4_43") (pintype "input"))
      (node (ref "SV204") (pin "8") (pinfunction "8_8") (pintype "passive"))
    )
    (net (code "46") (name "IO_IN3") (class "Default")
      (node (ref "IC201") (pin "3") (pinfunction "IP3_3") (pintype "input"))
      (node (ref "SV204") (pin "6") (pinfunction "6_6") (pintype "passive"))
    )
    (net (code "47") (name "IO_IN4") (class "Default")
      (node (ref "IC201") (pin "5") (pinfunction "IP1_5") (pintype "input"))
      (node (ref "SV204") (pin "4") (pinfunction "4_4") (pintype "passive"))
    )
    (net (code "48") (name "IO_IN5") (class "Default")
      (node (ref "IC201") (pin "8") (pinfunction "IP0_8") (pintype "input"))
      (node (ref "SV204") (pin "2") (pinfunction "2_2") (pintype "passive"))
    )
    (net (code "49") (name "IO_OUT0") (class "Default")
      (node (ref "IC201") (pin "31") (pinfunction "OP2_31") (pintype "output"))
      (node (ref "SV204") (pin "11") (pinfunction "11_11") (pintype "passive"))
    )
    (net (code "50") (name "IO_OUT1") (class "Default")
      (node (ref "IC201") (pin "32") (pinfunction "OP0_32") (pintype "output"))
      (node (ref "SV204") (pin "9") (pinfunction "9_9") (pintype "passive"))
    )
    (net (code "51") (name "IO_OUT2") (class "Default")
      (node (ref "IC201") (pin "29") (pinfunction "OP6_29") (pintype "output"))
      (node (ref "SV204") (pin "7") (pinfunction "7_7") (pintype "passive"))
    )
    (net (code "52") (name "IO_OUT3") (class "Default")
      (node (ref "IC201") (pin "30") (pinfunction "OP4_30") (pintype "output"))
      (node (ref "SV204") (pin "5") (pinfunction "5_5") (pintype "passive"))
    )
    (net (code "53") (name "IO_OUT4") (class "Default")
      (node (ref "IC201") (pin "14") (pinfunction "OP1_14") (pintype "output"))
      (node (ref "SV204") (pin "3") (pinfunction "3_3") (pintype "passive"))
    )
    (net (code "54") (name "IO_OUT5") (class "Default")
      (node (ref "IC201") (pin "16") (pinfunction "OP5_16") (pintype "output"))
      (node (ref "SV204") (pin "1") (pinfunction "1_1") (pintype "passive"))
    )
    (net (code "55") (name "Net-(C201-Pad2)") (class "Default")
      (node (ref "C201") (pin "2") (pinfunction "2_2") (pintype "passive"))
      (node (ref "Q201") (pin "2") (pinfunction "2_2") (pintype "passive"))
      (node (ref "R203") (pin "1") (pinfunction "1_1") (pintype "passive"))
    )
    (net (code "56") (name "Net-(C202-Pad2)") (class "Default")
      (node (ref "C202") (pin "2") (pinfunction "2_2") (pintype "passive"))
      (node (ref "Q201") (pin "1") (pinfunction "1_1") (pintype "passive"))
      (node (ref "R204") (pin "1") (pinfunction "1_1") (pintype "passive"))
    )
    (net (code "57") (name "Net-(IC303A-D2)") (class "Default")
      (node (ref "IC303") (pin "2") (pinfunction "Q1_2") (pintype "output"))
      (node (ref "IC303") (pin "5") (pinfunction "D2_5") (pintype "input"))
    )
    (net (code "58") (name "Net-(IC303A-D3)") (class "Default")
      (node (ref "IC303") (pin "12") (pinfunction "D3_12") (pintype "input"))
      (node (ref "IC303") (pin "7") (pinfunction "Q2_7") (pintype "output"))
    )
    (net (code "59") (name "Net-(IC303A-D4)") (class "Default")
      (node (ref "IC303") (pin "10") (pinfunction "Q3_10") (pintype "output"))
      (node (ref "IC303") (pin "13") (pinfunction "D4_13") (pintype "input"))
    )
    (net (code "60") (name "Net-(IC304-DIS)") (class "Default")
      (node (ref "C304") (pin "1") (pinfunction "1_1") (pintype "passive"))
      (node (ref "IC304") (pin "6") (pinfunction "TRE_6") (pintype "input"))
      (node (ref "IC304") (pin "7") (pinfunction "DIS_7") (pintype "input"))
      (node (ref "R302") (pin "2") (pinfunction "2_2") (pintype "passive"))
    )
    (net (code "61") (name "Net-(IC304-TRI)") (class "Default")
      (node (ref "C303") (pin "1") (pinfunction "1_1") (pintype "passive"))
      (node (ref "IC304") (pin "2") (pinfunction "TRI_2") (pintype "input"))
      (node (ref "R301") (pin "2") (pinfunction "2_2") (pintype "passive"))
      (node (ref "S301") (pin "1") (pinfunction "S_1") (pintype "passive"))
      (node (ref "S301") (pin "2") (pinfunction "S1_2") (pintype "passive"))
    )
    (net (code "62") (name "Net-(LED101-PadA)") (class "Default")
      (node (ref "LED101") (pin "A") (pinfunction "A_A") (pintype "passive"))
      (node (ref "R114") (pin "2") (pinfunction "2_2") (pintype "passive"))
    )
    (net (code "63") (name "Net-(LED201-PadA)") (class "Default")
      (node (ref "LED201") (pin "A") (pinfunction "A_A") (pintype "passive"))
      (node (ref "R205") (pin "2") (pinfunction "2_2") (pintype "passive"))
    )
    (net (code "64") (name "Net-(LED202-PadA)") (class "Default")
      (node (ref "LED202") (pin "A") (pinfunction "A_A") (pintype "passive"))
      (node (ref "R206") (pin "2") (pinfunction "2_2") (pintype "passive"))
    )
    (net (code "65") (name "RESET") (class "Default")
      (node (ref "IC302") (pin "9") (pinfunction "IN9_9") (pintype "input"))
      (node (ref "IC304") (pin "3") (pinfunction "OUT_3") (pintype "output"))
    )
    (net (code "66") (name "R{slash}~{W}") (class "Default")
      (node (ref "IC101") (pin "30") (pinfunction "R/~{W}_30") (pintype "output"))
      (node (ref "IC102") (pin "29") (pinfunction "~{WE}_29") (pintype "input"))
      (node (ref "IC103") (pin "31") (pinfunction "~{WE}_31") (pintype "input"))
      (node (ref "IC201") (pin "9") (pinfunction "R/~{W}_9") (pintype "input"))
      (node (ref "IC202") (pin "27") (pinfunction "~{WE}_27") (pintype "input"))
      (node (ref "IC301") (pin "5") (pinfunction "IN5_5") (pintype "input"))
      (node (ref "SV202") (pin "29") (pinfunction "29_29") (pintype "passive"))
    )
    (net (code "67") (name "STATUS0") (class "Default")
      (node (ref "IC201") (pin "15") (pinfunction "OP3_15") (pintype "output"))
      (node (ref "R206") (pin "1") (pinfunction "1_1") (pintype "passive"))
    )
    (net (code "68") (name "STATUS1") (class "Default")
      (node (ref "IC201") (pin "17") (pinfunction "OP7_17") (pintype "output"))
      (node (ref "R205") (pin "1") (pinfunction "1_1") (pintype "passive"))
    )
    (net (code "69") (name "UART0_RX") (class "Default")
      (node (ref "IC201") (pin "35") (pinfunction "RXDA_35") (pintype "input"))
      (node (ref "SV203") (pin "2") (pinfunction "2_2") (pintype "passive"))
    )
    (net (code "70") (name "UART0_TX") (class "Default")
      (node (ref "IC201") (pin "33") (pinfunction "TXDA_33") (pintype "output"))
      (node (ref "SV203") (pin "1") (pinfunction "1_1") (pintype "passive"))
    )
    (net (code "71") (name "UART1_RX") (class "Default")
      (node (ref "IC201") (pin "11") (pinfunction "RXDB_11") (pintype "output"))
      (node (ref "SV203") (pin "4") (pinfunction "4_4") (pintype "passive"))
    )
    (net (code "72") (name "UART1_TX") (class "Default")
      (node (ref "IC201") (pin "13") (pinfunction "TXDB_13") (pintype "bidirectional"))
      (node (ref "SV203") (pin "3") (pinfunction "3_3") (pintype "passive"))
    )
    (net (code "73") (name "unconnected-(IC301-IO21-Pad21)") (class "Default")
      (node (ref "IC301") (pin "21") (pinfunction "IO21_21") (pintype "bidirectional"))
    )
    (net (code "74") (name "unconnected-(IC302-IO14-Pad14)") (class "Default")
      (node (ref "IC302") (pin "14") (pinfunction "IO14_14") (pintype "bidirectional"))
    )
    (net (code "75") (name "unconnected-(IC302-IO15-Pad15)") (class "Default")
      (node (ref "IC302") (pin "15") (pinfunction "IO15_15") (pintype "bidirectional"))
    )
    (net (code "76") (name "unconnected-(IC302-IO16-Pad16)") (class "Default")
      (node (ref "IC302") (pin "16") (pinfunction "IO16_16") (pintype "bidirectional"))
    )
    (net (code "77") (name "unconnected-(IC303A-Q4-Pad15)") (class "Default")
      (node (ref "IC303") (pin "15") (pinfunction "Q4_15") (pintype "output"))
    )
    (net (code "78") (name "unconnected-(IC303A-~{Q1}-Pad3)") (class "Default")
      (node (ref "IC303") (pin "3") (pinfunction "~{Q1}_3") (pintype "output"))
    )
    (net (code "79") (name "unconnected-(IC303A-~{Q2}-Pad6)") (class "Default")
      (node (ref "IC303") (pin "6") (pinfunction "~{Q2}_6") (pintype "output"))
    )
    (net (code "80") (name "unconnected-(IC303A-~{Q3}-Pad11)") (class "Default")
      (node (ref "IC303") (pin "11") (pinfunction "~{Q3}_11") (pintype "output"))
    )
    (net (code "81") (name "unconnected-(Q101-TS-Pad1)") (class "Default")
      (node (ref "Q101") (pin "1") (pinfunction "TS_1") (pintype "passive"))
    )
    (net (code "82") (name "~{68681_CS}") (class "Default")
      (node (ref "IC201") (pin "39") (pinfunction "~{CS}_39") (pintype "input"))
      (node (ref "IC301") (pin "14") (pinfunction "IO14_14") (pintype "bidirectional"))
    )
    (net (code "83") (name "~{68681_DTACK}") (class "Default")
      (node (ref "IC201") (pin "10") (pinfunction "~{DTACK}_10") (pintype "output"))
      (node (ref "IC302") (pin "11") (pinfunction "IN11_11") (pintype "input"))
      (node (ref "R201") (pin "1") (pinfunction "1_1") (pintype "passive"))
    )
    (net (code "84") (name "~{68681_IACK}") (class "Default")
      (node (ref "IC201") (pin "41") (pinfunction "~{IACK}_41") (pintype "input"))
      (node (ref "IC302") (pin "10") (pinfunction "IN10_10") (pintype "input"))
    )
    (net (code "85") (name "~{68681_IRQ}") (class "Default")
      (node (ref "IC201") (pin "24") (pinfunction "~{INTR}_24") (pintype "output"))
      (node (ref "IC302") (pin "13") (pinfunction "IN13_13") (pintype "input"))
      (node (ref "R202") (pin "1") (pinfunction "1_1") (pintype "passive"))
    )
    (net (code "86") (name "~{AS}") (class "Default")
      (node (ref "IC101") (pin "28") (pinfunction "AS_28") (pintype "output"))
      (node (ref "IC301") (pin "6") (pinfunction "IN6_6") (pintype "input"))
      (node (ref "SV202") (pin "33") (pinfunction "33_33") (pintype "passive"))
    )
    (net (code "87") (name "~{BERR_TIMER_CLR}") (class "Default")
      (node (ref "IC301") (pin "22") (pinfunction "IO22_22") (pintype "bidirectional"))
      (node (ref "IC303") (pin "1") (pinfunction "CLR_1") (pintype "input"))
    )
    (net (code "88") (name "~{BERR}") (class "Default")
      (node (ref "IC101") (pin "40") (pinfunction "BERR_40") (pintype "input"))
      (node (ref "IC302") (pin "17") (pinfunction "IO17_17") (pintype "bidirectional"))
      (node (ref "IC303") (pin "14") (pinfunction "~{Q4}_14") (pintype "output"))
      (node (ref "R113") (pin "2") (pinfunction "2_2") (pintype "passive"))
      (node (ref "SV202") (pin "9") (pinfunction "9_9") (pintype "passive"))
    )
    (net (code "89") (name "~{BG}") (class "Default")
      (node (ref "IC101") (pin "32") (pinfunction "BG_32") (pintype "output"))
      (node (ref "SV202") (pin "25") (pinfunction "25_25") (pintype "passive"))
    )
    (net (code "90") (name "~{BR}") (class "Default")
      (node (ref "IC101") (pin "33") (pinfunction "BR_33") (pintype "input"))
      (node (ref "R111") (pin "2") (pinfunction "2_2") (pintype "passive"))
      (node (ref "SV202") (pin "23") (pinfunction "23_23") (pintype "passive"))
    )
    (net (code "91") (name "~{BUS_CS}") (class "Default")
      (node (ref "IC301") (pin "23") (pinfunction "IO23_23") (pintype "bidirectional"))
      (node (ref "SV201") (pin "7") (pinfunction "7_7") (pintype "passive"))
    )
    (net (code "92") (name "~{BUS_DTACK}") (class "Default")
      (node (ref "IC302") (pin "4") (pinfunction "IN4_4") (pintype "input"))
      (node (ref "SV201") (pin "6") (pinfunction "6_6") (pintype "passive"))
    )
    (net (code "93") (name "~{BUS_IRQ}") (class "Default")
      (node (ref "IC302") (pin "5") (pinfunction "IN5_5") (pintype "input"))
      (node (ref "SV201") (pin "5") (pinfunction "5_5") (pintype "passive"))
    )
    (net (code "94") (name "~{DS}") (class "Default")
      (node (ref "IC101") (pin "29") (pinfunction "DS_29") (pintype "output"))
      (node (ref "SV202") (pin "31") (pinfunction "31_31") (pintype "passive"))
    )
    (net (code "95") (name "~{DTACK}") (class "Default")
      (node (ref "IC101") (pin "31") (pinfunction "DTACK_31") (pintype "input"))
      (node (ref "IC302") (pin "20") (pinfunction "IO20_20") (pintype "bidirectional"))
      (node (ref "SV202") (pin "27") (pinfunction "27_27") (pintype "passive"))
    )
    (net (code "96") (name "~{HALT}") (class "Default")
      (node (ref "IC101") (pin "36") (pinfunction "HALT_36") (pintype "bidirectional"))
      (node (ref "IC302") (pin "21") (pinfunction "IO21_21") (pintype "bidirectional"))
      (node (ref "R102") (pin "1") (pinfunction "1_1") (pintype "passive"))
      (node (ref "SV202") (pin "17") (pinfunction "17_17") (pintype "passive"))
    )
    (net (code "97") (name "~{IACK}") (class "Default")
      (node (ref "IC301") (pin "19") (pinfunction "IO19_19") (pintype "bidirectional"))
      (node (ref "IC302") (pin "7") (pinfunction "IN7_7") (pintype "input"))
    )
    (net (code "98") (name "~{IPL0{slash}2}") (class "Default")
      (node (ref "IC101") (pin "42") (pinfunction "IPL0/2_42") (pintype "input"))
      (node (ref "IC302") (pin "19") (pinfunction "IO19_19") (pintype "bidirectional"))
    )
    (net (code "99") (name "~{IPL1}") (class "Default")
      (node (ref "IC101") (pin "41") (pinfunction "IPL1_41") (pintype "input"))
      (node (ref "IC302") (pin "18") (pinfunction "IO18_18") (pintype "bidirectional"))
    )
    (net (code "100") (name "~{OE}") (class "Default")
      (node (ref "IC102") (pin "24") (pinfunction "~{OE}_24") (pintype "input"))
      (node (ref "IC103") (pin "24") (pinfunction "~{OE}_24") (pintype "input"))
      (node (ref "IC202") (pin "22") (pinfunction "~{OE}_22") (pintype "input"))
      (node (ref "IC301") (pin "18") (pinfunction "IO18_18") (pintype "bidirectional"))
    )
    (net (code "101") (name "~{RAM_CS}") (class "Default")
      (node (ref "IC102") (pin "22") (pinfunction "~{CE1}_22") (pintype "input"))
      (node (ref "IC301") (pin "16") (pinfunction "IO16_16") (pintype "bidirectional"))
    )
    (net (code "102") (name "~{REQUIRE_DTACK}") (class "Default")
      (node (ref "IC301") (pin "20") (pinfunction "IO20_20") (pintype "bidirectional"))
      (node (ref "IC302") (pin "6") (pinfunction "IN6_6") (pintype "input"))
    )
    (net (code "103") (name "~{RESET}") (class "Default")
      (node (ref "IC101") (pin "37") (pinfunction "RESET_37") (pintype "bidirectional"))
      (node (ref "IC201") (pin "38") (pinfunction "~{RESET}_38") (pintype "input"))
      (node (ref "IC302") (pin "22") (pinfunction "IO22_22") (pintype "bidirectional"))
      (node (ref "R101") (pin "1") (pinfunction "1_1") (pintype "passive"))
      (node (ref "SV202") (pin "15") (pinfunction "15_15") (pintype "passive"))
    )
    (net (code "104") (name "~{ROM_CS}") (class "Default")
      (node (ref "IC103") (pin "22") (pinfunction "~{CS}_22") (pintype "input"))
      (node (ref "IC301") (pin "17") (pinfunction "IO17_17") (pintype "bidirectional"))
    )
    (net (code "105") (name "~{RTC_CS}") (class "Default")
      (node (ref "IC202") (pin "20") (pinfunction "~{CS}_20") (pintype "input"))
      (node (ref "IC301") (pin "15") (pinfunction "IO15_15") (pintype "bidirectional"))
    )
    (net (code "106") (name "~{VPA}") (class "Default")
      (node (ref "IC101") (pin "39") (pinfunction "VPA_39") (pintype "input"))
      (node (ref "IC302") (pin "23") (pinfunction "IO23_23") (pintype "bidirectional"))
      (node (ref "R112") (pin "2") (pinfunction "2_2") (pintype "passive"))
      (node (ref "SV202") (pin "11") (pinfunction "11_11") (pintype "passive"))
    )
  )
)
